# AFE.net
KiCad netlist of a schematic drawn in Altium Designer
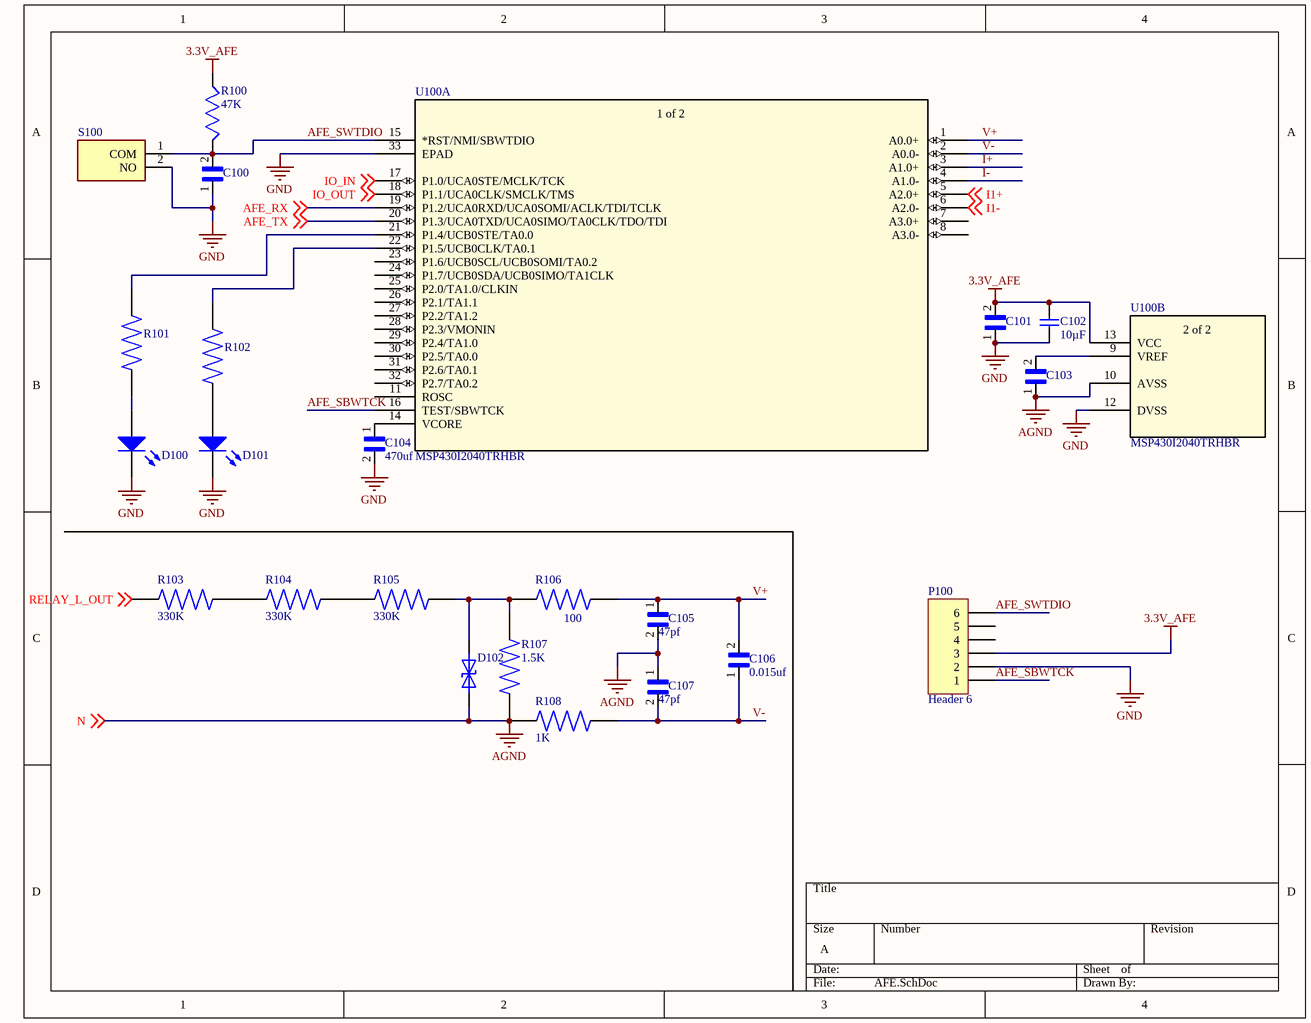
[diagram p0: AFE.SchDoc]

(export (version "E")
  (design (tool "Eeschema 10.0.6"))
  (components
    (comp (ref "C100")
      (value "06033G104ZAT4A")
      (footprint "cahrgebot_digital:CAPC1608X90N")
      (description "Cap Ceramic 0.1uF 25V Y5V -20% to 80% SMD 0603 85C T/R")
      (fields (field (name "MF") "{'manufacturer': u'AVX'}"))
      (libsource (lib "SnapEDA_Library") (part "06033G104ZAT4A"))
    )
    (comp (ref "C101")
      (value "06033G104ZAT4A")
      (footprint "CAPC1608X90N")
      (description "Cap Ceramic 0.1uF 25V Y5V -20% to 80% SMD 0603 85C T/R")
      (fields (field (name "MF") "{'manufacturer': u'AVX'}"))
      (libsource (lib "SnapEDA_Library") (part "06033G104ZAT4A"))
    )
    (comp (ref "C102")
      (value "10µF")
      (footprint "CAP_0603 - duplicate")
      (description "10µF 10V Ceramic Capacitor X5R 0603 (1608 Metric) 0.063\" L x 0.031\" W (1.60mm x 0.80mm)")
      (fields
        (field (name "MANUFACTURER") "Samsung Electronics")
        (field (name "PART NUMBER") "CL10A106KP8NNNC")
      )
      (libsource (lib "apollo2-amaph1kk-kbr-brd") (part "CL10A106KP8NNNC"))
    )
    (comp (ref "C103")
      (value "06033G104ZAT4A")
      (footprint "CAPC1608X90N")
      (description "Cap Ceramic 0.1uF 25V Y5V -20% to 80% SMD 0603 85C T/R")
      (fields (field (name "MF") "{'manufacturer': u'AVX'}"))
      (libsource (lib "SnapEDA_Library") (part "06033G104ZAT4A"))
    )
    (comp (ref "C104")
      (value "470uf")
      (footprint "CAPC1608X90")
      (description "CAP, MLCC, X5R, 0.47UF, 10V, 0603")
      (fields (field (name "MP") "C0603C474K8PACTU") (field (name "MF") "{'manufacturer': u'KEMET'}"))
      (libsource (lib "SnapEDA_Library") (part "C0603C474K8PACTU"))
    )
    (comp (ref "C105")
      (value "47pf")
      (footprint "CAPC1608X90")
      (description "CAP CER 47PF 50V C0G/NPO 0603")
      (fields (field (name "MP") "CC0603JRNPO9BN470") (field (name "MF") "{'manufacturer': u'Yageo'}"))
      (libsource (lib "SnapEDA_Library") (part "CC0603JRNPO9BN470"))
    )
    (comp (ref "C106")
      (value "0.015uf")
      (footprint "CAPC1608X87N")
      (description "VJ_W1BC")
      (fields
        (field (name "MP") "VJ0603Y153KXAPW1BC")
        (field (name "MF") "{'manufacturer': u'Vishay Vitramon'}")
      )
      (libsource (lib "SnapEDA_Library") (part "VJ0603Y153KXAPW1BC"))
    )
    (comp (ref "C107")
      (value "47pf")
      (footprint "CAPC1608X90")
      (description "CAP CER 47PF 50V C0G/NPO 0603")
      (fields (field (name "MP") "CC0603JRNPO9BN470") (field (name "MF") "{'manufacturer': u'Yageo'}"))
      (libsource (lib "SnapEDA_Library") (part "CC0603JRNPO9BN470"))
    )
    (comp (ref "D100")
      (value "LED-BLUE")
      (footprint "LED-0603-BLUE")
      (description "Blue 470nm LED Indication - Discrete 2.8V 0603 (1608 Metric)")
      (fields (field (name "PART NUMBER") "LTST-C193TBKT-5A") (field (name "MANUFACTURER") "Lite-On"))
      (libsource (lib "apollo2-amaph1kk-kbr-brd") (part "LTST-C193TBKT-5A"))
    )
    (comp (ref "D101")
      (value "LED-BLUE")
      (footprint "LED-0603-BLUE")
      (description "Blue 470nm LED Indication - Discrete 2.8V 0603 (1608 Metric)")
      (fields (field (name "PART NUMBER") "LTST-C193TBKT-5A") (field (name "MANUFACTURER") "Lite-On"))
      (libsource (lib "apollo2-amaph1kk-kbr-brd") (part "LTST-C193TBKT-5A"))
    )
    (comp (ref "D102")
      (value "SMAJ5.0CA-13-F")
      (footprint "DIOM5126X229N")
      (description "9.2V Clamp 43.5A Ipp Tvs Diode Surface Mount SMA (DO-214AC)")
      (fields (field (name "MF") "{'manufacturer': u'Diodes Inc.'}"))
      (libsource (lib "SnapEDA_Library") (part "SMAJ5.0CA-13-F"))
    )
    (comp (ref "P100")
      (value "Header 6")
      (footprint "HDR1X6 - duplicate")
      (description "Header, 6-Pin")
      (fields (field (name "PUBLISHER") "Altium Limited"))
      (libsource (lib "Miscellaneous Connectors") (part "Header 6"))
    )
    (comp (ref "R100")
      (value "47K")
      (footprint "RESC1608X55 - duplicate")
      (description "RC Series 0603 0.1 W 47 kOhms 1% Â±100 ppm/Â°C SMT Thick Film Chip Resistor")
      (fields (field (name "MP") "RC0603FR-0747KL") (field (name "MF") "{'manufacturer': u'Yageo'}"))
      (libsource (lib "SnapEDA_Library") (part "RC0603FR-0747KL"))
    )
    (comp (ref "R101")
      (value "SR0603KR-7W270RL")
      (footprint "RESC1608X55 - duplicate")
      (fields (field (name "MF") "{'manufacturer': u'Yageo'}"))
      (libsource (lib "SnapEDA_Library") (part "SR0603KR-7W270RL"))
    )
    (comp (ref "R102")
      (value "SR0603KR-7W270RL")
      (footprint "RESC1608X55 - duplicate")
      (fields (field (name "MF") "{'manufacturer': u'Yageo'}"))
      (libsource (lib "SnapEDA_Library") (part "SR0603KR-7W270RL"))
    )
    (comp (ref "R103")
      (value "330K")
      (footprint "RESC6331X70N")
      (fields (field (name "MP") "CRCW2512330KFKEG") (field (name "MF") "{'manufacturer': u'Vishay'}"))
      (libsource (lib "SnapEDA_Library") (part "CRCW2512330KFKEG"))
    )
    (comp (ref "R104")
      (value "330K")
      (footprint "RESC6331X70N")
      (fields (field (name "MP") "CRCW2512330KFKEG") (field (name "MF") "{'manufacturer': u'Vishay'}"))
      (libsource (lib "SnapEDA_Library") (part "CRCW2512330KFKEG"))
    )
    (comp (ref "R105")
      (value "330K")
      (footprint "RESC6331X70N")
      (fields (field (name "MP") "CRCW2512330KFKEG") (field (name "MF") "{'manufacturer': u'Vishay'}"))
      (libsource (lib "SnapEDA_Library") (part "CRCW2512330KFKEG"))
    )
    (comp (ref "R106")
      (value "100")
      (footprint "RESC1608X55N - duplicate")
      (description "SMD 0603 thick film resistor 100R 1%")
      (fields (field (name "MP") "CR0603-FX-1000ELF") (field (name "MF") "{'manufacturer': u'Bourns'}"))
      (libsource (lib "SnapEDA_Library") (part "CR0603-FX-1000ELF"))
    )
    (comp (ref "R107")
      (value "1.5K")
      (footprint "RESC6331X70N")
      (fields (field (name "MP") "CRCW25121K50JNEG") (field (name "MF") "{'manufacturer': u'Vishay'}"))
      (libsource (lib "SnapEDA_Library") (part "CRCW25121K50JNEG"))
    )
    (comp (ref "R108")
      (value "1K")
      (footprint "RESC1608X55N - duplicate")
      (description "Resistor; Thick Film; Res 1 Kilohms; Pwr-Rtg 0.1 W; Tol 1%; SMT; 0603")
      (fields (field (name "MP") "CR0603-FX-1001ELF") (field (name "MF") "{'manufacturer': u'Bourns'}"))
      (libsource (lib "SnapEDA_Library") (part "CR0603-FX-1001ELF"))
    )
    (comp (ref "S100")
      (value "PTS636_SM43_SMTR_LFS")
      (footprint "PTS636SM43SMTRLFS - duplicate")
      (description "Switch")
      (fields
        (field (name "MANUFACTURER_PART_NUMBER") "PTS636 SM43 SMTR LFS")
        (field (name "MOUSER PART NUMBER") "611-PTS636SM43SMTRLF")
      )
      (libsource (lib "mouser_sch_lib") (part "PTS636_SM43_SMTR_LFS"))
    )
    (comp (ref "U100")
      (value "MSP430I2040TRHBR")
      (footprint "RHB32_TEX")
      (description "No Description Available")
      (fields (field (name "COPYRIGHT") "Copyright (C) 2022 Ultra Librarian. All rights reserved."))
      (libsource (lib "MSP430I2040TRHBR") (part "MSP430I2040TRHBR"))
    )
  )
  (nets
    (net (code "1") (name "/AFE_SBWTCK") (class "Default")
      (node (ref "P100") (pin "1") (pinfunction "1_1") (pintype "passive"))
      (node (ref "U100") (pin "16") (pinfunction "TEST/SBWTCK_16") (pintype "passive"))
    )
    (net (code "2") (name "/AFE_SWTDIO") (class "Default")
      (node (ref "C100") (pin "2") (pinfunction "2_2") (pintype "passive"))
      (node (ref "P100") (pin "6") (pinfunction "6_6") (pintype "passive"))
      (node (ref "R100") (pin "1") (pinfunction "1_1") (pintype "passive"))
      (node (ref "S100") (pin "1") (pinfunction "COM_1") (pintype "passive"))
      (node (ref "U100") (pin "15") (pinfunction "*RST/NMI/SBWTDIO_15") (pintype "passive"))
    )
    (net (code "3") (name "/I+") (class "Default")
      (node (ref "U100") (pin "3") (pinfunction "A1.0+_3") (pintype "bidirectional"))
    )
    (net (code "4") (name "/I-") (class "Default")
      (node (ref "U100") (pin "4") (pinfunction "A1.0-_4") (pintype "bidirectional"))
    )
    (net (code "5") (name "/V+") (class "Default")
      (node (ref "C105") (pin "1") (pinfunction "1_1") (pintype "passive"))
      (node (ref "C106") (pin "2") (pinfunction "2_2") (pintype "passive"))
      (node (ref "R106") (pin "2") (pinfunction "2_2") (pintype "passive"))
      (node (ref "U100") (pin "1") (pinfunction "A0.0+_1") (pintype "bidirectional"))
    )
    (net (code "6") (name "/V-") (class "Default")
      (node (ref "C106") (pin "1") (pinfunction "1_1") (pintype "passive"))
      (node (ref "C107") (pin "2") (pinfunction "2_2") (pintype "passive"))
      (node (ref "R108") (pin "2") (pinfunction "2_2") (pintype "passive"))
      (node (ref "U100") (pin "2") (pinfunction "A0.0-_2") (pintype "bidirectional"))
    )
    (net (code "7") (name "3.3V_AFE") (class "Default")
      (node (ref "C101") (pin "2") (pinfunction "2_2") (pintype "passive"))
      (node (ref "C102") (pin "1") (pinfunction "1_1") (pintype "passive"))
      (node (ref "P100") (pin "3") (pinfunction "3_3") (pintype "passive"))
      (node (ref "R100") (pin "2") (pinfunction "2_2") (pintype "passive"))
      (node (ref "U100") (pin "13") (pinfunction "VCC_13") (pintype "power_in"))
    )
    (net (code "8") (name "AFE_RX") (class "Default")
      (node (ref "U100") (pin "19") (pinfunction "P1.2/UCA0RXD/UCA0SOMI/ACLK/TDI/TCLK_19") (pintype "bidirectional"))
    )
    (net (code "9") (name "AFE_TX") (class "Default")
      (node (ref "U100") (pin "20") (pinfunction "P1.3/UCA0TXD/UCA0SIMO/TA0CLK/TDO/TDI_20") (pintype "bidirectional"))
    )
    (net (code "10") (name "AGND") (class "Default")
      (node (ref "C103") (pin "1") (pinfunction "1_1") (pintype "passive"))
      (node (ref "C105") (pin "2") (pinfunction "2_2") (pintype "passive"))
      (node (ref "C107") (pin "1") (pinfunction "1_1") (pintype "passive"))
      (node (ref "D102") (pin "2") (pinfunction "2_2") (pintype "passive"))
      (node (ref "R107") (pin "1") (pinfunction "1_1") (pintype "passive"))
      (node (ref "R108") (pin "1") (pinfunction "1_1") (pintype "passive"))
      (node (ref "U100") (pin "10") (pinfunction "AVSS_10") (pintype "passive"))
    )
    (net (code "11") (name "GND") (class "Default")
      (node (ref "C100") (pin "1") (pinfunction "1_1") (pintype "passive"))
      (node (ref "C101") (pin "1") (pinfunction "1_1") (pintype "passive"))
      (node (ref "C102") (pin "2") (pinfunction "2_2") (pintype "passive"))
      (node (ref "C104") (pin "2") (pinfunction "2_2") (pintype "passive"))
      (node (ref "D100") (pin "2") (pinfunction "K_2") (pintype "passive"))
      (node (ref "D101") (pin "2") (pinfunction "K_2") (pintype "passive"))
      (node (ref "P100") (pin "2") (pinfunction "2_2") (pintype "passive"))
      (node (ref "S100") (pin "2") (pinfunction "NO_2") (pintype "passive"))
      (node (ref "U100") (pin "12") (pinfunction "DVSS_12") (pintype "passive"))
      (node (ref "U100") (pin "33") (pinfunction "EPAD_33") (pintype "passive"))
    )
    (net (code "12") (name "I1+") (class "Default")
      (node (ref "U100") (pin "5") (pinfunction "A2.0+_5") (pintype "bidirectional"))
    )
    (net (code "13") (name "I1-") (class "Default")
      (node (ref "U100") (pin "6") (pinfunction "A2.0-_6") (pintype "bidirectional"))
    )
    (net (code "14") (name "IO_IN") (class "Default")
      (node (ref "U100") (pin "17") (pinfunction "P1.0/UCA0STE/MCLK/TCK_17") (pintype "bidirectional"))
    )
    (net (code "15") (name "IO_OUT") (class "Default")
      (node (ref "U100") (pin "18") (pinfunction "P1.1/UCA0CLK/SMCLK/TMS_18") (pintype "bidirectional"))
    )
    (net (code "16") (name "Net-(D100-A)") (class "Default")
      (node (ref "D100") (pin "1") (pinfunction "A_1") (pintype "passive"))
      (node (ref "R101") (pin "1") (pinfunction "1_1") (pintype "passive"))
    )
    (net (code "17") (name "Net-(D101-A)") (class "Default")
      (node (ref "D101") (pin "1") (pinfunction "A_1") (pintype "passive"))
      (node (ref "R102") (pin "1") (pinfunction "1_1") (pintype "passive"))
    )
    (net (code "18") (name "Net-(D102-Pad1)") (class "Default")
      (node (ref "D102") (pin "1") (pinfunction "1_1") (pintype "passive"))
      (node (ref "R105") (pin "2") (pinfunction "2_2") (pintype "passive"))
      (node (ref "R106") (pin "1") (pinfunction "1_1") (pintype "passive"))
      (node (ref "R107") (pin "2") (pinfunction "2_2") (pintype "passive"))
    )
    (net (code "19") (name "Net-(R103-Pad2)") (class "Default")
      (node (ref "R103") (pin "2") (pinfunction "2_2") (pintype "passive"))
      (node (ref "R104") (pin "1") (pinfunction "1_1") (pintype "passive"))
    )
    (net (code "20") (name "Net-(R104-Pad2)") (class "Default")
      (node (ref "R104") (pin "2") (pinfunction "2_2") (pintype "passive"))
      (node (ref "R105") (pin "1") (pinfunction "1_1") (pintype "passive"))
    )
    (net (code "21") (name "Net-(U100A-P1.4{slash}UCB0STE{slash}TA0.0)") (class "Default")
      (node (ref "R101") (pin "2") (pinfunction "2_2") (pintype "passive"))
      (node (ref "U100") (pin "21") (pinfunction "P1.4/UCB0STE/TA0.0_21") (pintype "bidirectional"))
    )
    (net (code "22") (name "Net-(U100A-P1.5{slash}UCB0CLK{slash}TA0.1)") (class "Default")
      (node (ref "R102") (pin "2") (pinfunction "2_2") (pintype "passive"))
      (node (ref "U100") (pin "22") (pinfunction "P1.5/UCB0CLK/TA0.1_22") (pintype "bidirectional"))
    )
    (net (code "23") (name "Net-(U100A-VCORE)") (class "Default")
      (node (ref "C104") (pin "1") (pinfunction "1_1") (pintype "passive"))
      (node (ref "U100") (pin "14") (pinfunction "VCORE_14") (pintype "passive"))
    )
    (net (code "24") (name "Net-(U100B-VREF)") (class "Default")
      (node (ref "C103") (pin "2") (pinfunction "2_2") (pintype "passive"))
      (node (ref "U100") (pin "9") (pinfunction "VREF_9") (pintype "power_in"))
    )
    (net (code "25") (name "RELAY_L_OUT") (class "Default")
      (node (ref "R103") (pin "1") (pinfunction "1_1") (pintype "passive"))
    )
    (net (code "26") (name "unconnected-(P100-Pad4)") (class "Default")
      (node (ref "P100") (pin "4") (pinfunction "4_4") (pintype "passive"))
    )
    (net (code "27") (name "unconnected-(P100-Pad5)") (class "Default")
      (node (ref "P100") (pin "5") (pinfunction "5_5") (pintype "passive"))
    )
    (net (code "28") (name "unconnected-(U100A-A3.0+-Pad7)") (class "Default")
      (node (ref "U100") (pin "7") (pinfunction "A3.0+_7") (pintype "bidirectional"))
    )
    (net (code "29") (name "unconnected-(U100A-A3.0--Pad8)") (class "Default")
      (node (ref "U100") (pin "8") (pinfunction "A3.0-_8") (pintype "bidirectional"))
    )
    (net (code "30") (name "unconnected-(U100A-P1.6{slash}UCB0SCL{slash}UCB0SOMI{slash}TA0.2-Pad23)") (class "Default")
      (node (ref "U100") (pin "23") (pinfunction "P1.6/UCB0SCL/UCB0SOMI/TA0.2_23") (pintype "bidirectional"))
    )
    (net (code "31") (name "unconnected-(U100A-P1.7{slash}UCB0SDA{slash}UCB0SIMO{slash}TA1CLK-Pad24)") (class "Default")
      (node (ref "U100") (pin "24") (pinfunction "P1.7/UCB0SDA/UCB0SIMO/TA1CLK_24") (pintype "bidirectional"))
    )
    (net (code "32") (name "unconnected-(U100A-P2.0{slash}TA1.0{slash}CLKIN-Pad25)") (class "Default")
      (node (ref "U100") (pin "25") (pinfunction "P2.0/TA1.0/CLKIN_25") (pintype "bidirectional"))
    )
    (net (code "33") (name "unconnected-(U100A-P2.1{slash}TA1.1-Pad26)") (class "Default")
      (node (ref "U100") (pin "26") (pinfunction "P2.1/TA1.1_26") (pintype "bidirectional"))
    )
    (net (code "34") (name "unconnected-(U100A-P2.2{slash}TA1.2-Pad27)") (class "Default")
      (node (ref "U100") (pin "27") (pinfunction "P2.2/TA1.2_27") (pintype "bidirectional"))
    )
    (net (code "35") (name "unconnected-(U100A-P2.3{slash}VMONIN-Pad28)") (class "Default")
      (node (ref "U100") (pin "28") (pinfunction "P2.3/VMONIN_28") (pintype "bidirectional"))
    )
    (net (code "36") (name "unconnected-(U100A-P2.4{slash}TA1.0-Pad29)") (class "Default")
      (node (ref "U100") (pin "29") (pinfunction "P2.4/TA1.0_29") (pintype "bidirectional"))
    )
    (net (code "37") (name "unconnected-(U100A-P2.5{slash}TA0.0-Pad30)") (class "Default")
      (node (ref "U100") (pin "30") (pinfunction "P2.5/TA0.0_30") (pintype "bidirectional"))
    )
    (net (code "38") (name "unconnected-(U100A-P2.6{slash}TA0.1-Pad31)") (class "Default")
      (node (ref "U100") (pin "31") (pinfunction "P2.6/TA0.1_31") (pintype "bidirectional"))
    )
    (net (code "39") (name "unconnected-(U100A-P2.7{slash}TA0.2-Pad32)") (class "Default")
      (node (ref "U100") (pin "32") (pinfunction "P2.7/TA0.2_32") (pintype "bidirectional"))
    )
    (net (code "40") (name "unconnected-(U100A-ROSC-Pad11)") (class "Default")
      (node (ref "U100") (pin "11") (pinfunction "ROSC_11") (pintype "passive"))
    )
  )
)
